# P9_MIDI.net
KiCad netlist of a schematic drawn in Altium Designer
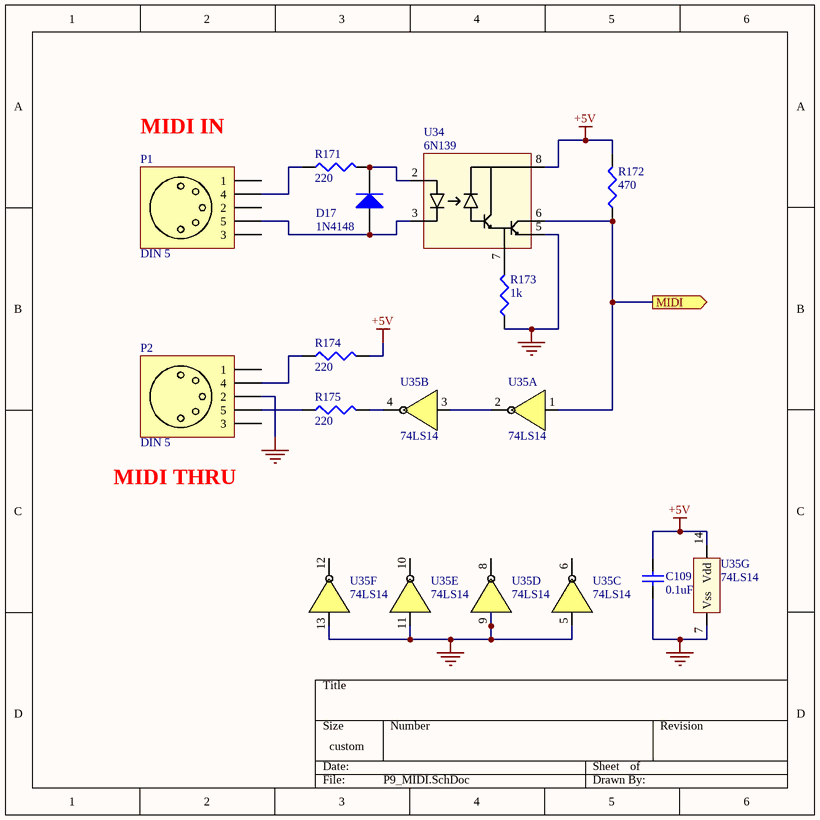
[diagram p0: P9_MIDI.SchDoc]

(export (version "E")
  (design (tool "Eeschema 10.0.6"))
  (components
    (comp (ref "C109")
      (value "0.1uF")
      (footprint "CAP 0603 (1608 metric)")
      (description "Capacitor (Semiconductor SIM Model)")
      (libsource (lib "Miscellaneous Devices") (part "Cap Semi"))
    )
    (comp (ref "D17")
      (value "1N4148")
      (description "High Conductance Fast Diode")
      (libsource (lib "Miscellaneous Devices") (part "Diode 1N4148"))
    )
    (comp (ref "P1") (value "DIN 5") (description "DIN 5pin") (libsource (lib "FilterPoC") (part "DIN 5pin")))
    (comp (ref "P2") (value "DIN 5") (description "DIN 5pin") (libsource (lib "FilterPoC") (part "DIN 5pin")))
    (comp (ref "R171")
      (value "220")
      (footprint "RES 0603 (1608 metric)")
      (description "Resistor")
      (libsource (lib "Miscellaneous Devices") (part "Res3"))
    )
    (comp (ref "R172")
      (value "470")
      (footprint "RES 0603 (1608 metric)")
      (description "Resistor")
      (libsource (lib "Miscellaneous Devices") (part "Res3"))
    )
    (comp (ref "R173")
      (value "1k")
      (footprint "RES 0603 (1608 metric)")
      (description "Resistor")
      (libsource (lib "Miscellaneous Devices") (part "Res3"))
    )
    (comp (ref "R174")
      (value "220")
      (footprint "RES 0603 (1608 metric)")
      (description "Resistor")
      (libsource (lib "Miscellaneous Devices") (part "Res3"))
    )
    (comp (ref "R175")
      (value "220")
      (footprint "RES 0603 (1608 metric)")
      (description "Resistor")
      (libsource (lib "Miscellaneous Devices") (part "Res3"))
    )
    (comp (ref "U34")
      (value "6N139")
      (description "Optocoupler")
      (libsource (lib "FilterPoC") (part "6N139"))
    )
    (comp (ref "U35") (value "74LS14") (description "Hex Inverter") (libsource (lib "") (part "74LS14_3")))
  )
  (nets
    (net (code "1") (name "+5V") (class "Default")
      (node (ref "C109") (pin "1") (pinfunction "1_1") (pintype "passive"))
      (node (ref "R172") (pin "2") (pinfunction "2_2") (pintype "passive"))
      (node (ref "R174") (pin "2") (pinfunction "2_2") (pintype "passive"))
      (node (ref "U34") (pin "8") (pinfunction "B1_8") (pintype "passive"))
      (node (ref "U35") (pin "14") (pinfunction "Vdd_14") (pintype "power_in"))
    )
    (net (code "2") (name "/MIDI") (class "Default")
      (node (ref "R172") (pin "1") (pinfunction "1_1") (pintype "passive"))
      (node (ref "U34") (pin "6") (pinfunction "B1_6") (pintype "passive"))
      (node (ref "U35") (pin "1") (pinfunction "A_1") (pintype "passive"))
    )
    (net (code "3") (name "GND") (class "Default")
      (node (ref "C109") (pin "2") (pinfunction "2_2") (pintype "passive"))
      (node (ref "P2") (pin "2") (pinfunction "2_2") (pintype "passive"))
      (node (ref "R173") (pin "1") (pinfunction "1_1") (pintype "passive"))
      (node (ref "U34") (pin "5") (pinfunction "B1_5") (pintype "passive"))
      (node (ref "U35") (pin "11") (pinfunction "E_11") (pintype "passive"))
      (node (ref "U35") (pin "13") (pinfunction "F_13") (pintype "passive"))
      (node (ref "U35") (pin "5") (pinfunction "C_5") (pintype "passive"))
      (node (ref "U35") (pin "7") (pinfunction "Vss_7") (pintype "power_in"))
      (node (ref "U35") (pin "9") (pinfunction "D_9") (pintype "passive"))
    )
    (net (code "4") (name "Net-(D17-A)") (class "Default")
      (node (ref "D17") (pin "1") (pinfunction "A_1") (pintype "passive"))
      (node (ref "P1") (pin "5") (pinfunction "5_5") (pintype "passive"))
      (node (ref "U34") (pin "3") (pinfunction "B1_3") (pintype "passive"))
    )
    (net (code "5") (name "Net-(D17-K)") (class "Default")
      (node (ref "D17") (pin "2") (pinfunction "K_2") (pintype "passive"))
      (node (ref "R171") (pin "2") (pinfunction "2_2") (pintype "passive"))
      (node (ref "U34") (pin "2") (pinfunction "B2_2") (pintype "passive"))
    )
    (net (code "6") (name "Net-(P1-Pad4)") (class "Default")
      (node (ref "P1") (pin "4") (pinfunction "4_4") (pintype "passive"))
      (node (ref "R171") (pin "1") (pinfunction "1_1") (pintype "passive"))
    )
    (net (code "7") (name "Net-(P2-Pad4)") (class "Default")
      (node (ref "P2") (pin "4") (pinfunction "4_4") (pintype "passive"))
      (node (ref "R174") (pin "1") (pinfunction "1_1") (pintype "passive"))
    )
    (net (code "8") (name "Net-(P2-Pad5)") (class "Default")
      (node (ref "P2") (pin "5") (pinfunction "5_5") (pintype "passive"))
      (node (ref "R175") (pin "1") (pinfunction "1_1") (pintype "passive"))
    )
    (net (code "9") (name "Net-(R173-Pad2)") (class "Default")
      (node (ref "R173") (pin "2") (pinfunction "2_2") (pintype "passive"))
      (node (ref "U34") (pin "7") (pinfunction "B1_7") (pintype "passive"))
    )
    (net (code "10") (name "Net-(U35A-~{A})") (class "Default")
      (node (ref "U35") (pin "2") (pinfunction "~{A}_2") (pintype "passive"))
      (node (ref "U35") (pin "3") (pinfunction "B_3") (pintype "passive"))
    )
    (net (code "11") (name "Net-(U35B-~{B})") (class "Default")
      (node (ref "R175") (pin "2") (pinfunction "2_2") (pintype "passive"))
      (node (ref "U35") (pin "4") (pinfunction "~{B}_4") (pintype "passive"))
    )
    (net (code "12") (name "unconnected-(P1-Pad1)") (class "Default")
      (node (ref "P1") (pin "1") (pinfunction "1_1") (pintype "passive"))
    )
    (net (code "13") (name "unconnected-(P1-Pad2)") (class "Default")
      (node (ref "P1") (pin "2") (pinfunction "2_2") (pintype "passive"))
    )
    (net (code "14") (name "unconnected-(P1-Pad3)") (class "Default")
      (node (ref "P1") (pin "3") (pinfunction "3_3") (pintype "passive"))
    )
    (net (code "15") (name "unconnected-(P2-Pad1)") (class "Default")
      (node (ref "P2") (pin "1") (pinfunction "1_1") (pintype "passive"))
    )
    (net (code "16") (name "unconnected-(P2-Pad3)") (class "Default")
      (node (ref "P2") (pin "3") (pinfunction "3_3") (pintype "passive"))
    )
    (net (code "17") (name "unconnected-(U35C-~{C}-Pad6)") (class "Default")
      (node (ref "U35") (pin "6") (pinfunction "~{C}_6") (pintype "passive"))
    )
    (net (code "18") (name "unconnected-(U35D-~{D}-Pad8)") (class "Default")
      (node (ref "U35") (pin "8") (pinfunction "~{D}_8") (pintype "passive"))
    )
    (net (code "19") (name "unconnected-(U35E-~{E}-Pad10)") (class "Default")
      (node (ref "U35") (pin "10") (pinfunction "~{E}_10") (pintype "passive"))
    )
    (net (code "20") (name "unconnected-(U35F-~{F}-Pad12)") (class "Default")
      (node (ref "U35") (pin "12") (pinfunction "~{F}_12") (pintype "passive"))
    )
  )
)
